# SCH_LED_7_SEG.net
KiCad netlist of a schematic drawn in Altium Designer
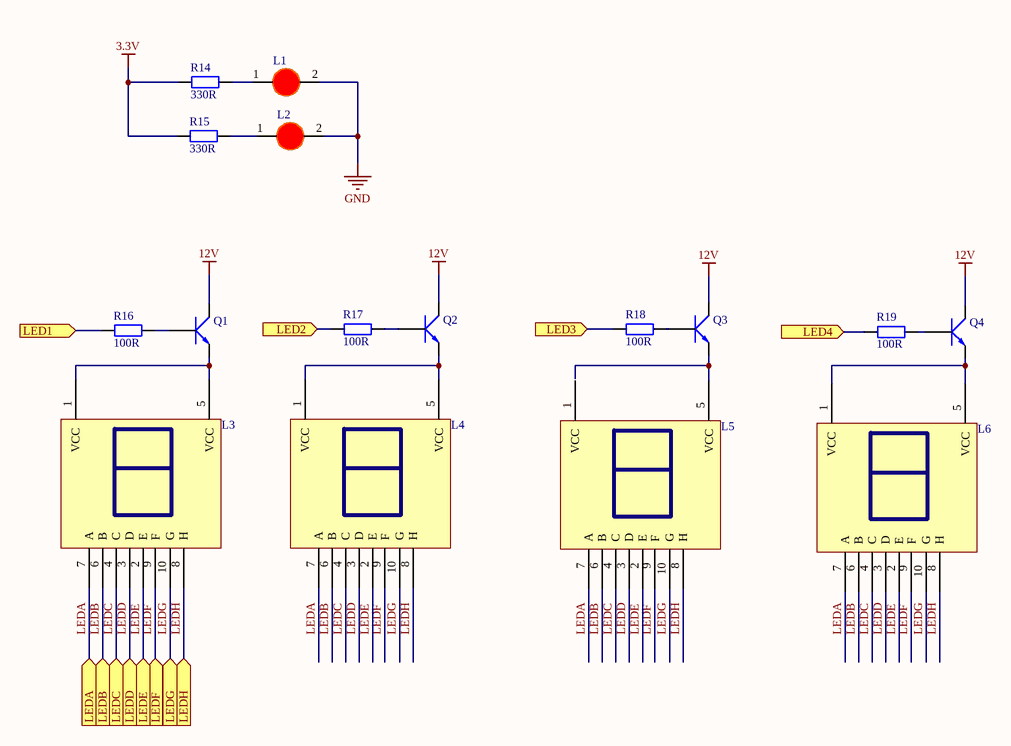
[diagram p0: SCH_LED_7_SEG.SchDoc]

(export (version "E")
  (design (tool "Eeschema 10.0.6"))
  (components
    (comp (ref "L1")
      (value "~")
      (footprint "LED-3MM-RED")
      (description "Cắm")
      (libsource (lib "Altium_Lib_by_KhueNguyenCreator") (part "LED 3mm Do"))
    )
    (comp (ref "L2")
      (value "~")
      (footprint "LED-3MM-RED")
      (description "Cắm")
      (libsource (lib "Altium_Lib_by_KhueNguyenCreator") (part "LED 3mm Do"))
    )
    (comp (ref "L3")
      (value "~")
      (footprint "LED7SEG_2.3inch")
      (description "Dán")
      (libsource (lib "Altium_Lib_by_KhueNguyenCreator") (part "LED 7x1 2.3inch Anot"))
    )
    (comp (ref "L4")
      (value "~")
      (footprint "LED7SEG_2.3inch")
      (description "Dán")
      (libsource (lib "Altium_Lib_by_KhueNguyenCreator") (part "LED 7x1 2.3inch Anot"))
    )
    (comp (ref "L5")
      (value "~")
      (footprint "LED7SEG_2.3inch")
      (description "Dán")
      (libsource (lib "Altium_Lib_by_KhueNguyenCreator") (part "LED 7x1 2.3inch Anot"))
    )
    (comp (ref "L6")
      (value "~")
      (footprint "LED7SEG_2.3inch")
      (description "Dán")
      (libsource (lib "Altium_Lib_by_KhueNguyenCreator") (part "LED 7x1 2.3inch Anot"))
    )
    (comp (ref "Q1")
      (value "~")
      (footprint "SOT23")
      (description "NPN transistor")
      (libsource (lib "Altium_Lib_by_KhueNguyenCreator") (part "C1815 HF SMD"))
    )
    (comp (ref "Q2")
      (value "~")
      (footprint "SOT23")
      (description "NPN transistor")
      (libsource (lib "Altium_Lib_by_KhueNguyenCreator") (part "C1815 HF SMD"))
    )
    (comp (ref "Q3")
      (value "~")
      (footprint "SOT23")
      (description "NPN transistor")
      (libsource (lib "Altium_Lib_by_KhueNguyenCreator") (part "C1815 HF SMD"))
    )
    (comp (ref "Q4")
      (value "~")
      (footprint "SOT23")
      (description "NPN transistor")
      (libsource (lib "Altium_Lib_by_KhueNguyenCreator") (part "C1815 HF SMD"))
    )
    (comp (ref "R14")
      (value "330R")
      (footprint "tro smd 0603")
      (description "Dán")
      (libsource (lib "Altium_Lib_by_KhueNguyenCreator") (part "Tro 0603 5% 330R"))
    )
    (comp (ref "R15")
      (value "330R")
      (footprint "tro smd 0603")
      (description "Dán")
      (libsource (lib "Altium_Lib_by_KhueNguyenCreator") (part "Tro 0603 5% 330R"))
    )
    (comp (ref "R16")
      (value "100R")
      (footprint "tro smd 0805")
      (description "Dán")
      (libsource (lib "Altium_Lib_by_KhueNguyenCreator") (part "Tro 0805 5% 100R"))
    )
    (comp (ref "R17")
      (value "100R")
      (footprint "tro smd 0805")
      (description "Dán")
      (libsource (lib "Altium_Lib_by_KhueNguyenCreator") (part "Tro 0805 5% 100R"))
    )
    (comp (ref "R18")
      (value "100R")
      (footprint "tro smd 0805")
      (description "Dán")
      (libsource (lib "Altium_Lib_by_KhueNguyenCreator") (part "Tro 0805 5% 100R"))
    )
    (comp (ref "R19")
      (value "100R")
      (footprint "tro smd 0805")
      (description "Dán")
      (libsource (lib "Altium_Lib_by_KhueNguyenCreator") (part "Tro 0805 5% 100R"))
    )
  )
  (nets
    (net (code "1") (name "/LED1") (class "Default")
      (node (ref "R16") (pin "1") (pinfunction "1_1") (pintype "passive"))
    )
    (net (code "2") (name "/LED2") (class "Default")
      (node (ref "R17") (pin "1") (pinfunction "1_1") (pintype "passive"))
    )
    (net (code "3") (name "/LED3") (class "Default")
      (node (ref "R18") (pin "1") (pinfunction "1_1") (pintype "passive"))
    )
    (net (code "4") (name "/LED4") (class "Default")
      (node (ref "R19") (pin "1") (pinfunction "1_1") (pintype "passive"))
    )
    (net (code "5") (name "/LEDA") (class "Default")
      (node (ref "L3") (pin "7") (pinfunction "A_7") (pintype "passive"))
      (node (ref "L4") (pin "7") (pinfunction "A_7") (pintype "passive"))
      (node (ref "L5") (pin "7") (pinfunction "A_7") (pintype "passive"))
      (node (ref "L6") (pin "7") (pinfunction "A_7") (pintype "passive"))
    )
    (net (code "6") (name "/LEDB") (class "Default")
      (node (ref "L3") (pin "6") (pinfunction "B_6") (pintype "passive"))
      (node (ref "L4") (pin "6") (pinfunction "B_6") (pintype "passive"))
      (node (ref "L5") (pin "6") (pinfunction "B_6") (pintype "passive"))
      (node (ref "L6") (pin "6") (pinfunction "B_6") (pintype "passive"))
    )
    (net (code "7") (name "/LEDC") (class "Default")
      (node (ref "L3") (pin "4") (pinfunction "C_4") (pintype "passive"))
      (node (ref "L4") (pin "4") (pinfunction "C_4") (pintype "passive"))
      (node (ref "L5") (pin "4") (pinfunction "C_4") (pintype "passive"))
      (node (ref "L6") (pin "4") (pinfunction "C_4") (pintype "passive"))
    )
    (net (code "8") (name "/LEDD") (class "Default")
      (node (ref "L3") (pin "3") (pinfunction "D_3") (pintype "passive"))
      (node (ref "L4") (pin "3") (pinfunction "D_3") (pintype "passive"))
      (node (ref "L5") (pin "3") (pinfunction "D_3") (pintype "passive"))
      (node (ref "L6") (pin "3") (pinfunction "D_3") (pintype "passive"))
    )
    (net (code "9") (name "/LEDE") (class "Default")
      (node (ref "L3") (pin "2") (pinfunction "E_2") (pintype "passive"))
      (node (ref "L4") (pin "2") (pinfunction "E_2") (pintype "passive"))
      (node (ref "L5") (pin "2") (pinfunction "E_2") (pintype "passive"))
      (node (ref "L6") (pin "2") (pinfunction "E_2") (pintype "passive"))
    )
    (net (code "10") (name "/LEDF") (class "Default")
      (node (ref "L3") (pin "9") (pinfunction "F_9") (pintype "passive"))
      (node (ref "L4") (pin "9") (pinfunction "F_9") (pintype "passive"))
      (node (ref "L5") (pin "9") (pinfunction "F_9") (pintype "passive"))
      (node (ref "L6") (pin "9") (pinfunction "F_9") (pintype "passive"))
    )
    (net (code "11") (name "/LEDG") (class "Default")
      (node (ref "L3") (pin "10") (pinfunction "G_10") (pintype "passive"))
      (node (ref "L4") (pin "10") (pinfunction "G_10") (pintype "passive"))
      (node (ref "L5") (pin "10") (pinfunction "G_10") (pintype "passive"))
      (node (ref "L6") (pin "10") (pinfunction "G_10") (pintype "passive"))
    )
    (net (code "12") (name "/LEDH") (class "Default")
      (node (ref "L3") (pin "8") (pinfunction "H_8") (pintype "passive"))
      (node (ref "L4") (pin "8") (pinfunction "H_8") (pintype "passive"))
      (node (ref "L5") (pin "8") (pinfunction "H_8") (pintype "passive"))
      (node (ref "L6") (pin "8") (pinfunction "H_8") (pintype "passive"))
    )
    (net (code "13") (name "3.3V") (class "Default")
      (node (ref "R14") (pin "1") (pinfunction "1_1") (pintype "passive"))
      (node (ref "R15") (pin "1") (pinfunction "1_1") (pintype "passive"))
    )
    (net (code "14") (name "12V") (class "Default")
      (node (ref "Q1") (pin "3") (pinfunction "C_3") (pintype "passive"))
      (node (ref "Q2") (pin "3") (pinfunction "C_3") (pintype "passive"))
      (node (ref "Q3") (pin "3") (pinfunction "C_3") (pintype "passive"))
      (node (ref "Q4") (pin "3") (pinfunction "C_3") (pintype "passive"))
    )
    (net (code "15") (name "GND") (class "Default")
      (node (ref "L1") (pin "2") (pinfunction "K_2") (pintype "passive"))
      (node (ref "L2") (pin "2") (pinfunction "K_2") (pintype "passive"))
    )
    (net (code "16") (name "Net-(L1-A)") (class "Default")
      (node (ref "L1") (pin "1") (pinfunction "A_1") (pintype "passive"))
      (node (ref "R14") (pin "2") (pinfunction "2_2") (pintype "passive"))
    )
    (net (code "17") (name "Net-(L2-A)") (class "Default")
      (node (ref "L2") (pin "1") (pinfunction "A_1") (pintype "passive"))
      (node (ref "R15") (pin "2") (pinfunction "2_2") (pintype "passive"))
    )
    (net (code "18") (name "Net-(Q1-B)") (class "Default")
      (node (ref "Q1") (pin "1") (pinfunction "B_1") (pintype "passive"))
      (node (ref "R16") (pin "2") (pinfunction "2_2") (pintype "passive"))
    )
    (net (code "19") (name "Net-(Q1-E)") (class "Default")
      (node (ref "L3") (pin "1") (pinfunction "VCC_1") (pintype "passive"))
      (node (ref "L3") (pin "5") (pinfunction "VCC_5") (pintype "passive"))
      (node (ref "Q1") (pin "2") (pinfunction "E_2") (pintype "passive"))
    )
    (net (code "20") (name "Net-(Q2-B)") (class "Default")
      (node (ref "Q2") (pin "1") (pinfunction "B_1") (pintype "passive"))
      (node (ref "R17") (pin "2") (pinfunction "2_2") (pintype "passive"))
    )
    (net (code "21") (name "Net-(Q2-E)") (class "Default")
      (node (ref "L4") (pin "1") (pinfunction "VCC_1") (pintype "passive"))
      (node (ref "L4") (pin "5") (pinfunction "VCC_5") (pintype "passive"))
      (node (ref "Q2") (pin "2") (pinfunction "E_2") (pintype "passive"))
    )
    (net (code "22") (name "Net-(Q3-B)") (class "Default")
      (node (ref "Q3") (pin "1") (pinfunction "B_1") (pintype "passive"))
      (node (ref "R18") (pin "2") (pinfunction "2_2") (pintype "passive"))
    )
    (net (code "23") (name "Net-(Q3-E)") (class "Default")
      (node (ref "L5") (pin "5") (pinfunction "VCC_5") (pintype "passive"))
      (node (ref "Q3") (pin "2") (pinfunction "E_2") (pintype "passive"))
    )
    (net (code "24") (name "Net-(Q4-B)") (class "Default")
      (node (ref "Q4") (pin "1") (pinfunction "B_1") (pintype "passive"))
      (node (ref "R19") (pin "2") (pinfunction "2_2") (pintype "passive"))
    )
    (net (code "25") (name "Net-(Q4-E)") (class "Default")
      (node (ref "L6") (pin "1") (pinfunction "VCC_1") (pintype "passive"))
      (node (ref "L6") (pin "5") (pinfunction "VCC_5") (pintype "passive"))
      (node (ref "Q4") (pin "2") (pinfunction "E_2") (pintype "passive"))
    )
    (net (code "26") (name "unconnected-(L5-VCC-Pad1)") (class "Default")
      (node (ref "L5") (pin "1") (pinfunction "VCC_1") (pintype "passive"))
    )
  )
)
